# singlemod.net
KiCad netlist of a schematic drawn in EAGLE
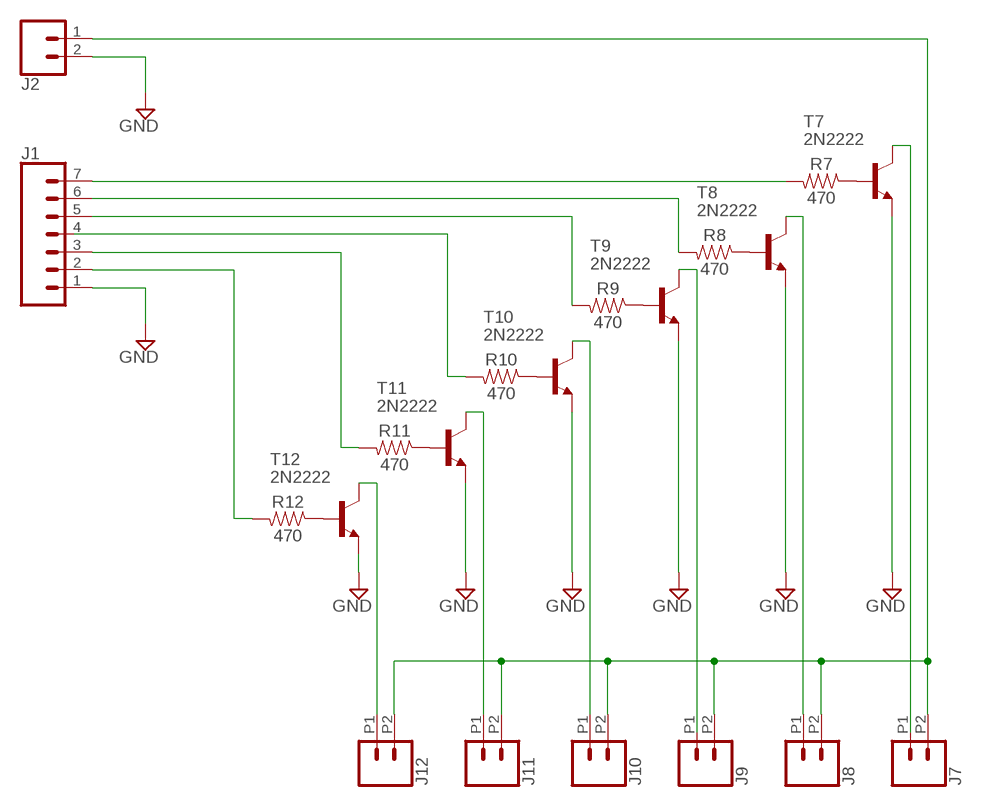
[diagram p0: schematic, sheet 1]

(export (version "E")
  (design (tool "Eeschema 10.0.6"))
  (components
    (comp (ref "J1")
      (value "CONN_07")
      (footprint "eagle-import:1X07")
      (libsource (lib "eagle-import") (part "CONN_07"))
    )
    (comp (ref "J2")
      (value "CONN_02")
      (footprint "eagle-import:1X02")
      (libsource (lib "eagle-import") (part "CONN_02"))
    )
    (comp (ref "J7")
      (value "CONN_022.54MM_SCREWTERM")
      (footprint "eagle-import:1X02_2.54_SCREWTERM")
      (libsource (lib "eagle-import") (part "CONN_022.54MM_SCREWTERM"))
    )
    (comp (ref "J8")
      (value "CONN_022.54MM_SCREWTERM")
      (footprint "eagle-import:1X02_2.54_SCREWTERM")
      (libsource (lib "eagle-import") (part "CONN_022.54MM_SCREWTERM"))
    )
    (comp (ref "J9")
      (value "CONN_022.54MM_SCREWTERM")
      (footprint "eagle-import:1X02_2.54_SCREWTERM")
      (libsource (lib "eagle-import") (part "CONN_022.54MM_SCREWTERM"))
    )
    (comp (ref "J10")
      (value "CONN_022.54MM_SCREWTERM")
      (footprint "eagle-import:1X02_2.54_SCREWTERM")
      (libsource (lib "eagle-import") (part "CONN_022.54MM_SCREWTERM"))
    )
    (comp (ref "J11")
      (value "CONN_022.54MM_SCREWTERM")
      (footprint "eagle-import:1X02_2.54_SCREWTERM")
      (libsource (lib "eagle-import") (part "CONN_022.54MM_SCREWTERM"))
    )
    (comp (ref "J12")
      (value "CONN_022.54MM_SCREWTERM")
      (footprint "eagle-import:1X02_2.54_SCREWTERM")
      (libsource (lib "eagle-import") (part "CONN_022.54MM_SCREWTERM"))
    )
    (comp (ref "R7")
      (value "470")
      (footprint "eagle-import:AXIAL-0.3")
      (libsource (lib "eagle-import") (part "1KOHM-HORIZ-1/4W-1%"))
    )
    (comp (ref "R8")
      (value "470")
      (footprint "eagle-import:AXIAL-0.3")
      (libsource (lib "eagle-import") (part "1KOHM-HORIZ-1/4W-1%"))
    )
    (comp (ref "R9")
      (value "470")
      (footprint "eagle-import:AXIAL-0.3")
      (libsource (lib "eagle-import") (part "1KOHM-HORIZ-1/4W-1%"))
    )
    (comp (ref "R10")
      (value "470")
      (footprint "eagle-import:AXIAL-0.3")
      (libsource (lib "eagle-import") (part "1KOHM-HORIZ-1/4W-1%"))
    )
    (comp (ref "R11")
      (value "470")
      (footprint "eagle-import:AXIAL-0.3")
      (libsource (lib "eagle-import") (part "1KOHM-HORIZ-1/4W-1%"))
    )
    (comp (ref "R12")
      (value "470")
      (footprint "eagle-import:AXIAL-0.3")
      (libsource (lib "eagle-import") (part "1KOHM-HORIZ-1/4W-1%"))
    )
    (comp (ref "T7")
      (value "2N2222")
      (footprint "eagle-import:TO92-EBC-OVAL")
      (libsource (lib "eagle-import") (part "2N2222"))
    )
    (comp (ref "T8")
      (value "2N2222")
      (footprint "eagle-import:TO92-EBC-OVAL")
      (libsource (lib "eagle-import") (part "2N2222"))
    )
    (comp (ref "T9")
      (value "2N2222")
      (footprint "eagle-import:TO92-EBC-OVAL")
      (libsource (lib "eagle-import") (part "2N2222"))
    )
    (comp (ref "T10")
      (value "2N2222")
      (footprint "eagle-import:TO92-EBC-OVAL")
      (libsource (lib "eagle-import") (part "2N2222"))
    )
    (comp (ref "T11")
      (value "2N2222")
      (footprint "eagle-import:TO92-EBC-OVAL")
      (libsource (lib "eagle-import") (part "2N2222"))
    )
    (comp (ref "T12")
      (value "2N2222")
      (footprint "eagle-import:TO92-EBC-OVAL")
      (libsource (lib "eagle-import") (part "2N2222"))
    )
  )
  (nets
    (net (code "1") (name "GND") (class "Default")
      (node (ref "J1") (pin "1") (pinfunction "1_1") (pintype "passive"))
      (node (ref "J2") (pin "2") (pinfunction "2_2") (pintype "passive"))
      (node (ref "T10") (pin "E") (pinfunction "E_E") (pintype "passive"))
      (node (ref "T11") (pin "E") (pinfunction "E_E") (pintype "passive"))
      (node (ref "T12") (pin "E") (pinfunction "E_E") (pintype "passive"))
      (node (ref "T7") (pin "E") (pinfunction "E_E") (pintype "passive"))
      (node (ref "T8") (pin "E") (pinfunction "E_E") (pintype "passive"))
      (node (ref "T9") (pin "E") (pinfunction "E_E") (pintype "passive"))
    )
    (net (code "2") (name "Net-(J7-1)") (class "Default")
      (node (ref "J7") (pin "P1") (pinfunction "1_P1") (pintype "passive"))
      (node (ref "T7") (pin "C") (pinfunction "C_C") (pintype "passive"))
    )
    (net (code "3") (name "Net-(J8-1)") (class "Default")
      (node (ref "J8") (pin "P1") (pinfunction "1_P1") (pintype "passive"))
      (node (ref "T8") (pin "C") (pinfunction "C_C") (pintype "passive"))
    )
    (net (code "4") (name "Net-(J9-1)") (class "Default")
      (node (ref "J9") (pin "P1") (pinfunction "1_P1") (pintype "passive"))
      (node (ref "T9") (pin "C") (pinfunction "C_C") (pintype "passive"))
    )
    (net (code "5") (name "Net-(J10-1)") (class "Default")
      (node (ref "J10") (pin "P1") (pinfunction "1_P1") (pintype "passive"))
      (node (ref "T10") (pin "C") (pinfunction "C_C") (pintype "passive"))
    )
    (net (code "6") (name "Net-(J10-2)") (class "Default")
      (node (ref "J10") (pin "P2") (pinfunction "2_P2") (pintype "passive"))
      (node (ref "J11") (pin "P2") (pinfunction "2_P2") (pintype "passive"))
      (node (ref "J12") (pin "P2") (pinfunction "2_P2") (pintype "passive"))
      (node (ref "J2") (pin "1") (pinfunction "1_1") (pintype "passive"))
      (node (ref "J7") (pin "P2") (pinfunction "2_P2") (pintype "passive"))
      (node (ref "J8") (pin "P2") (pinfunction "2_P2") (pintype "passive"))
      (node (ref "J9") (pin "P2") (pinfunction "2_P2") (pintype "passive"))
    )
    (net (code "7") (name "Net-(J11-1)") (class "Default")
      (node (ref "J11") (pin "P1") (pinfunction "1_P1") (pintype "passive"))
      (node (ref "T11") (pin "C") (pinfunction "C_C") (pintype "passive"))
    )
    (net (code "8") (name "Net-(J12-1)") (class "Default")
      (node (ref "J12") (pin "P1") (pinfunction "1_P1") (pintype "passive"))
      (node (ref "T12") (pin "C") (pinfunction "C_C") (pintype "passive"))
    )
    (net (code "9") (name "Net-(R7-1)") (class "Default")
      (node (ref "R7") (pin "P$1") (pinfunction "1_P$1") (pintype "passive"))
      (node (ref "T7") (pin "B") (pinfunction "B_B") (pintype "passive"))
    )
    (net (code "10") (name "Net-(R7-2)") (class "Default")
      (node (ref "J1") (pin "7") (pinfunction "7_7") (pintype "passive"))
      (node (ref "R7") (pin "P$2") (pinfunction "2_P$2") (pintype "passive"))
    )
    (net (code "11") (name "Net-(R8-1)") (class "Default")
      (node (ref "R8") (pin "P$1") (pinfunction "1_P$1") (pintype "passive"))
      (node (ref "T8") (pin "B") (pinfunction "B_B") (pintype "passive"))
    )
    (net (code "12") (name "Net-(R8-2)") (class "Default")
      (node (ref "J1") (pin "6") (pinfunction "6_6") (pintype "passive"))
      (node (ref "R8") (pin "P$2") (pinfunction "2_P$2") (pintype "passive"))
    )
    (net (code "13") (name "Net-(R9-1)") (class "Default")
      (node (ref "R9") (pin "P$1") (pinfunction "1_P$1") (pintype "passive"))
      (node (ref "T9") (pin "B") (pinfunction "B_B") (pintype "passive"))
    )
    (net (code "14") (name "Net-(R9-2)") (class "Default")
      (node (ref "J1") (pin "5") (pinfunction "5_5") (pintype "passive"))
      (node (ref "R9") (pin "P$2") (pinfunction "2_P$2") (pintype "passive"))
    )
    (net (code "15") (name "Net-(R10-1)") (class "Default")
      (node (ref "R10") (pin "P$1") (pinfunction "1_P$1") (pintype "passive"))
      (node (ref "T10") (pin "B") (pinfunction "B_B") (pintype "passive"))
    )
    (net (code "16") (name "Net-(R10-2)") (class "Default")
      (node (ref "J1") (pin "4") (pinfunction "4_4") (pintype "passive"))
      (node (ref "R10") (pin "P$2") (pinfunction "2_P$2") (pintype "passive"))
    )
    (net (code "17") (name "Net-(R11-1)") (class "Default")
      (node (ref "R11") (pin "P$1") (pinfunction "1_P$1") (pintype "passive"))
      (node (ref "T11") (pin "B") (pinfunction "B_B") (pintype "passive"))
    )
    (net (code "18") (name "Net-(R11-2)") (class "Default")
      (node (ref "J1") (pin "3") (pinfunction "3_3") (pintype "passive"))
      (node (ref "R11") (pin "P$2") (pinfunction "2_P$2") (pintype "passive"))
    )
    (net (code "19") (name "Net-(R12-1)") (class "Default")
      (node (ref "R12") (pin "P$1") (pinfunction "1_P$1") (pintype "passive"))
      (node (ref "T12") (pin "B") (pinfunction "B_B") (pintype "passive"))
    )
    (net (code "20") (name "Net-(R12-2)") (class "Default")
      (node (ref "J1") (pin "2") (pinfunction "2_2") (pintype "passive"))
      (node (ref "R12") (pin "P$2") (pinfunction "2_P$2") (pintype "passive"))
    )
  )
)
